# DS138-1_0-B.net
KiCad netlist of a schematic drawn in Altium Designer
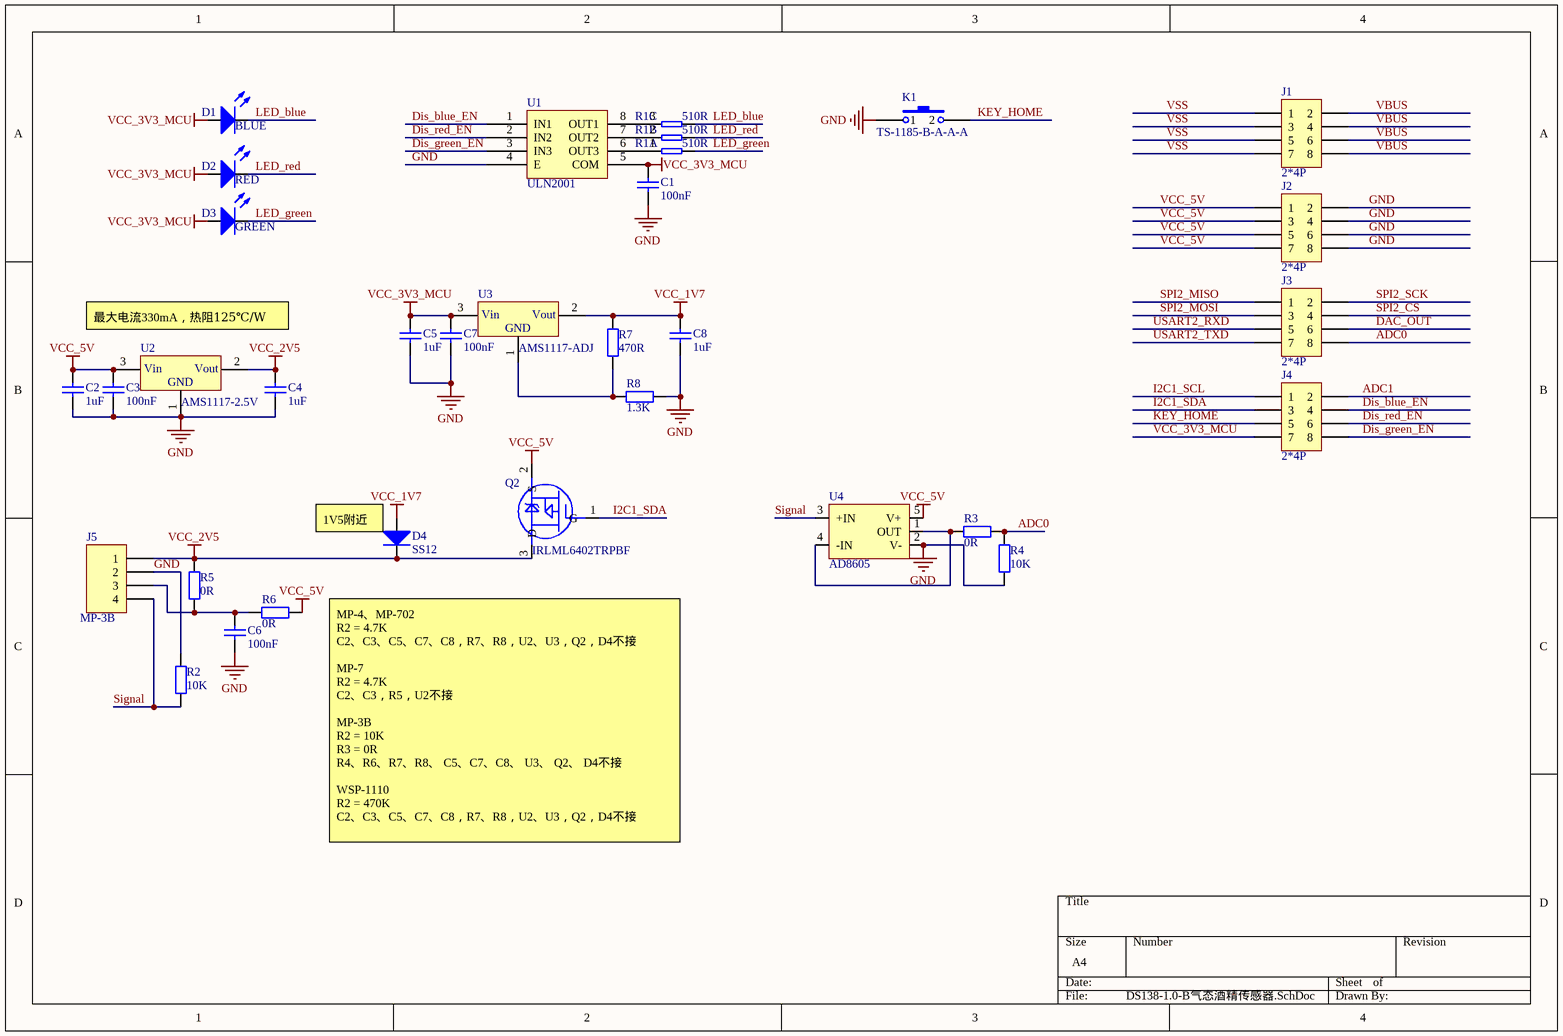
[diagram p0: DS138-1.0-B气态酒精传感器.SchDoc]

(export (version "E")
  (design (tool "Eeschema 10.0.6"))
  (components
    (comp (ref "C1")
      (value "100nF")
      (footprint "0603CAP")
      (description "贴片电容")
      (fields (field (name "Comment") "SMDCAP00013"))
      (libsource (lib "AD_SCH") (part "MLCC 100nF 50V ±10％ 0603"))
    )
    (comp (ref "C2")
      (value "1uF")
      (footprint "0603CAP")
      (description "贴片电容")
      (fields (field (name "Comment") "SMDCAP00015"))
      (libsource (lib "AD_SCH") (part "MLCC 1uF 50V ±10％ 0603"))
    )
    (comp (ref "C3")
      (value "100nF")
      (footprint "0603CAP")
      (description "贴片电容")
      (fields (field (name "Comment") "SMDCAP00013"))
      (libsource (lib "AD_SCH") (part "MLCC 100nF 50V ±10％ 0603"))
    )
    (comp (ref "C4")
      (value "1uF")
      (footprint "0603CAP")
      (description "贴片电容")
      (fields (field (name "Comment") "SMDCAP00015"))
      (libsource (lib "AD_SCH") (part "MLCC 1uF 50V ±10％ 0603"))
    )
    (comp (ref "C5")
      (value "1uF")
      (footprint "0603CAP")
      (description "贴片电容")
      (fields (field (name "Comment") "SMDCAP00015"))
      (libsource (lib "AD_SCH") (part "MLCC 1uF 50V ±10％ 0603"))
    )
    (comp (ref "C6")
      (value "100nF")
      (footprint "0603CAP")
      (description "贴片电容")
      (fields (field (name "Comment") "SMDCAP00013"))
      (libsource (lib "AD_SCH") (part "MLCC 100nF 50V ±10％ 0603"))
    )
    (comp (ref "C7")
      (value "100nF")
      (footprint "0603CAP")
      (description "贴片电容")
      (fields (field (name "Comment") "SMDCAP00013"))
      (libsource (lib "AD_SCH") (part "MLCC 100nF 50V ±10％ 0603"))
    )
    (comp (ref "C8")
      (value "1uF")
      (footprint "0603CAP")
      (description "贴片电容")
      (fields (field (name "Comment") "SMDCAP00015"))
      (libsource (lib "AD_SCH") (part "MLCC 1uF 50V ±10％ 0603"))
    )
    (comp (ref "D1")
      (value "BLUE")
      (footprint "LED_0805")
      (description "贴片LED")
      (fields (field (name "Comment") "SMDLED00010"))
      (libsource (lib "AD_SCH") (part "Chip 蓝色LED 0805"))
    )
    (comp (ref "D2")
      (value "RED")
      (footprint "LED_0805")
      (description "贴片LED")
      (fields (field (name "Comment") "SMDLED00003"))
      (libsource (lib "AD_SCH") (part "Chip 红色LED 0805"))
    )
    (comp (ref "D3")
      (value "GREEN")
      (footprint "LED_0805")
      (description "贴片LED")
      (fields (field (name "Comment") "Chip 翠绿LED 0805"))
      (libsource (lib "AD_SCH") (part "Chip 翠绿LED 0805"))
    )
    (comp (ref "D4")
      (value "SS12")
      (footprint "SMA/DO-214AC")
      (description "贴片肖特基二极管")
      (fields (field (name "Comment") "SMDDIODE06003"))
      (libsource (lib "AD_SCH") (part "SS12 SMA/DO-214AC（1N5817）"))
    )
    (comp (ref "J1")
      (value "2*4P")
      (footprint "X1321WVS-2x04J-C40D53")
      (description "双排针2x4P 立贴 1.27mm")
      (fields (field (name "Comment") "X1321WVS-2x04J-C40D53"))
      (libsource (lib "AD_SCH") (part "X1321WVS-2x04J-C40D53"))
    )
    (comp (ref "J2")
      (value "2*4P")
      (footprint "X1321WVS-2x04J-C40D53")
      (description "双排针2x4P 立贴 1.27mm")
      (fields (field (name "Comment") "X1321WVS-2x04J-C40D53"))
      (libsource (lib "AD_SCH") (part "X1321WVS-2x04J-C40D53"))
    )
    (comp (ref "J3")
      (value "2*4P")
      (footprint "X1321WVS-2x04J-C40D53")
      (description "双排针2x4P 立贴 1.27mm")
      (fields (field (name "Comment") "X1321WVS-2x04J-C40D53"))
      (libsource (lib "AD_SCH") (part "X1321WVS-2x04J-C40D53"))
    )
    (comp (ref "J4")
      (value "2*4P")
      (footprint "X1321WVS-2x04J-C40D53")
      (description "双排针2x4P 立贴 1.27mm")
      (fields (field (name "Comment") "X1321WVS-2x04J-C40D53"))
      (libsource (lib "AD_SCH") (part "X1321WVS-2x04J-C40D53"))
    )
    (comp (ref "J5")
      (value "MP-3B")
      (footprint "SIP4")
      (fields (field (name "Comment") "SL000000042"))
      (libsource (lib "AD_SCH") (part "DIP4 单排直针 间距2.54mm 针长11mm 铜"))
    )
    (comp (ref "K1")
      (value "TS-1185-B-A-A-A")
      (footprint "KEY_TS-1185-x-A-A-A")
      (description "轻触开关")
      (libsource (lib "AD_SCH") (part "TS-1185-B-A-A-A"))
    )
    (comp (ref "Q2")
      (value "IRLML6402TRPBF")
      (footprint "SOT23")
      (description "贴片P-MOS管")
      (fields (field (name "Comment") "SMDPMOS00001"))
      (libsource (lib "AD_SCH") (part "IRLML6402TRPBF SOT-23 IR"))
    )
    (comp (ref "R1")
      (value "510R")
      (footprint "0603RES_Pack4")
      (description "贴片排阻")
      (fields (field (name "Comment") "SMDRES05003"))
      (libsource (lib "AD_SCH") (part "Chip R*4 510R 1/16W ±5％ 0603"))
    )
    (comp (ref "R2")
      (value "10K")
      (footprint "0603RES")
      (description "贴片电阻")
      (fields (field (name "Comment") "SMDRES00056"))
      (libsource (lib "AD_SCH") (part "Chip 10K 1/16W ±1％ 0603"))
    )
    (comp (ref "R3")
      (value "0R")
      (footprint "0603RES")
      (description "贴片电阻")
      (fields (field (name "Comment") "Chip 0R 1/16W ±1％ 0603"))
      (libsource (lib "AD_SCH") (part "Chip 0R 1/16W ±1％ 0603"))
    )
    (comp (ref "R4")
      (value "10K")
      (footprint "0603RES")
      (description "贴片电阻")
      (fields (field (name "Comment") "SMDRES00056"))
      (libsource (lib "AD_SCH") (part "Chip 10K 1/16W ±1％ 0603"))
    )
    (comp (ref "R5")
      (value "0R")
      (footprint "0603RES")
      (description "贴片电阻")
      (fields (field (name "Comment") "Chip 0R 1/16W ±1％ 0603"))
      (libsource (lib "") (part "Chip 0R 1/16W ±1％ 0603_1"))
    )
    (comp (ref "R6")
      (value "0R")
      (footprint "0603RES")
      (description "贴片电阻")
      (fields (field (name "Comment") "Chip 0R 1/16W ±1％ 0603"))
      (libsource (lib "AD_SCH") (part "Chip 0R 1/16W ±1％ 0603"))
    )
    (comp (ref "R7")
      (value "470R")
      (footprint "0603RES")
      (description "贴片电阻")
      (fields (field (name "Comment") "SMDRES00027"))
      (libsource (lib "AD_SCH") (part "Chip 470R 1/16W ±1％ 0603"))
    )
    (comp (ref "R8")
      (value "1.3K")
      (footprint "0603RES")
      (description "贴片电阻")
      (fields (field (name "Comment") "SMDRES00038"))
      (libsource (lib "AD_SCH") (part "Chip 1.3K 1/16W ±1％ 0603"))
    )
    (comp (ref "U1")
      (value "ULN2001")
      (footprint "SO-8")
      (description "电机驱动芯片")
      (fields (field (name "Comment") "SMDIC000018"))
      (libsource (lib "AD_SCH") (part "ULN2001 SOP-8"))
    )
    (comp (ref "U2")
      (value "AMS1117-2.5V")
      (footprint "SOT223")
      (description "稳压芯片")
      (fields (field (name "Comment") "SMDIC000020"))
      (libsource (lib "AD_SCH") (part "AMS1117-3.3V SOT-223"))
    )
    (comp (ref "U3")
      (value "AMS1117-ADJ")
      (footprint "SOT223")
      (description "稳压芯片")
      (fields (field (name "Comment") "SMDIC000020"))
      (libsource (lib "AD_SCH") (part "AMS1117-3.3V SOT-223"))
    )
    (comp (ref "U4")
      (value "AD8605")
      (footprint "SOT23-5")
      (description "运放芯片")
      (libsource (lib "AD_SCH") (part "AD8605 SOT23-5"))
    )
  )
  (nets
    (net (code "1") (name "/ADC0") (class "Default")
      (node (ref "J3") (pin "8") (pinfunction "8_8") (pintype "passive"))
      (node (ref "R3") (pin "1") (pinfunction "1_1") (pintype "passive"))
      (node (ref "R4") (pin "1") (pinfunction "1_1") (pintype "passive"))
    )
    (net (code "2") (name "/ADC1") (class "Default")
      (node (ref "J4") (pin "2") (pinfunction "2_2") (pintype "passive"))
    )
    (net (code "3") (name "/DAC_OUT") (class "Default")
      (node (ref "J3") (pin "6") (pinfunction "6_6") (pintype "passive"))
    )
    (net (code "4") (name "/Dis_blue_EN") (class "Default")
      (node (ref "J4") (pin "4") (pinfunction "4_4") (pintype "passive"))
      (node (ref "U1") (pin "1") (pinfunction "IN1_1") (pintype "passive"))
    )
    (net (code "5") (name "/Dis_green_EN") (class "Default")
      (node (ref "J4") (pin "8") (pinfunction "8_8") (pintype "passive"))
      (node (ref "U1") (pin "3") (pinfunction "IN3_3") (pintype "passive"))
    )
    (net (code "6") (name "/Dis_red_EN") (class "Default")
      (node (ref "J4") (pin "6") (pinfunction "6_6") (pintype "passive"))
      (node (ref "U1") (pin "2") (pinfunction "IN2_2") (pintype "passive"))
    )
    (net (code "7") (name "/I2C1_SCL") (class "Default")
      (node (ref "J4") (pin "1") (pinfunction "1_1") (pintype "passive"))
    )
    (net (code "8") (name "/I2C1_SDA") (class "Default")
      (node (ref "J4") (pin "3") (pinfunction "3_3") (pintype "passive"))
      (node (ref "Q2") (pin "1") (pinfunction "G_1") (pintype "passive"))
    )
    (net (code "9") (name "/KEY_HOME") (class "Default")
      (node (ref "J4") (pin "5") (pinfunction "5_5") (pintype "passive"))
      (node (ref "K1") (pin "2") (pinfunction "2_2") (pintype "passive"))
    )
    (net (code "10") (name "/LED_blue") (class "Default")
      (node (ref "D1") (pin "2") (pinfunction "K_2") (pintype "passive"))
      (node (ref "R1") (pin "6") (pinfunction "6_6") (pintype "passive"))
    )
    (net (code "11") (name "/LED_green") (class "Default")
      (node (ref "D3") (pin "2") (pinfunction "K_2") (pintype "passive"))
      (node (ref "R1") (pin "8") (pinfunction "8_8") (pintype "passive"))
    )
    (net (code "12") (name "/LED_red") (class "Default")
      (node (ref "D2") (pin "2") (pinfunction "K_2") (pintype "passive"))
      (node (ref "R1") (pin "7") (pinfunction "7_7") (pintype "passive"))
    )
    (net (code "13") (name "/SPI2_CS") (class "Default")
      (node (ref "J3") (pin "4") (pinfunction "4_4") (pintype "passive"))
    )
    (net (code "14") (name "/SPI2_MISO") (class "Default")
      (node (ref "J3") (pin "1") (pinfunction "1_1") (pintype "passive"))
    )
    (net (code "15") (name "/SPI2_MOSI") (class "Default")
      (node (ref "J3") (pin "3") (pinfunction "3_3") (pintype "passive"))
    )
    (net (code "16") (name "/SPI2_SCK") (class "Default")
      (node (ref "J3") (pin "2") (pinfunction "2_2") (pintype "passive"))
    )
    (net (code "17") (name "/Signal") (class "Default")
      (node (ref "J5") (pin "4") (pinfunction "4_4") (pintype "passive"))
      (node (ref "R2") (pin "2") (pinfunction "2_2") (pintype "passive"))
      (node (ref "U4") (pin "3") (pinfunction "+IN_3") (pintype "passive"))
    )
    (net (code "18") (name "/USART2_RXD") (class "Default")
      (node (ref "J3") (pin "5") (pinfunction "5_5") (pintype "passive"))
    )
    (net (code "19") (name "/USART2_TXD") (class "Default")
      (node (ref "J3") (pin "7") (pinfunction "7_7") (pintype "passive"))
    )
    (net (code "20") (name "/VBUS") (class "Default")
      (node (ref "J1") (pin "2") (pinfunction "2_2") (pintype "passive"))
      (node (ref "J1") (pin "4") (pinfunction "4_4") (pintype "passive"))
      (node (ref "J1") (pin "6") (pinfunction "6_6") (pintype "passive"))
      (node (ref "J1") (pin "8") (pinfunction "8_8") (pintype "passive"))
    )
    (net (code "21") (name "/VSS") (class "Default")
      (node (ref "J1") (pin "1") (pinfunction "1_1") (pintype "passive"))
      (node (ref "J1") (pin "3") (pinfunction "3_3") (pintype "passive"))
      (node (ref "J1") (pin "5") (pinfunction "5_5") (pintype "passive"))
      (node (ref "J1") (pin "7") (pinfunction "7_7") (pintype "passive"))
    )
    (net (code "22") (name "GND") (class "Default")
      (node (ref "C1") (pin "1") (pinfunction "1_1") (pintype "passive"))
      (node (ref "C2") (pin "1") (pinfunction "1_1") (pintype "passive"))
      (node (ref "C3") (pin "1") (pinfunction "1_1") (pintype "passive"))
      (node (ref "C4") (pin "1") (pinfunction "1_1") (pintype "passive"))
      (node (ref "C5") (pin "1") (pinfunction "1_1") (pintype "passive"))
      (node (ref "C6") (pin "1") (pinfunction "1_1") (pintype "passive"))
      (node (ref "C7") (pin "1") (pinfunction "1_1") (pintype "passive"))
      (node (ref "C8") (pin "1") (pinfunction "1_1") (pintype "passive"))
      (node (ref "J2") (pin "2") (pinfunction "2_2") (pintype "passive"))
      (node (ref "J2") (pin "4") (pinfunction "4_4") (pintype "passive"))
      (node (ref "J2") (pin "6") (pinfunction "6_6") (pintype "passive"))
      (node (ref "J2") (pin "8") (pinfunction "8_8") (pintype "passive"))
      (node (ref "J5") (pin "2") (pinfunction "2_2") (pintype "passive"))
      (node (ref "K1") (pin "1") (pinfunction "1_1") (pintype "passive"))
      (node (ref "R2") (pin "1") (pinfunction "1_1") (pintype "passive"))
      (node (ref "R4") (pin "2") (pinfunction "2_2") (pintype "passive"))
      (node (ref "R8") (pin "2") (pinfunction "2_2") (pintype "passive"))
      (node (ref "U1") (pin "4") (pinfunction "E_4") (pintype "passive"))
      (node (ref "U2") (pin "1") (pinfunction "GND_1") (pintype "passive"))
      (node (ref "U4") (pin "2") (pinfunction "V-_2") (pintype "passive"))
    )
    (net (code "23") (name "Net-(C6-Pad2)") (class "Default")
      (node (ref "C6") (pin "2") (pinfunction "2_2") (pintype "passive"))
      (node (ref "J5") (pin "3") (pinfunction "3_3") (pintype "passive"))
      (node (ref "R5") (pin "1") (pinfunction "1_1") (pintype "passive"))
      (node (ref "R6") (pin "2") (pinfunction "2_2") (pintype "passive"))
    )
    (net (code "24") (name "Net-(U1-OUT1)") (class "Default")
      (node (ref "R1") (pin "3") (pinfunction "3_3") (pintype "passive"))
      (node (ref "U1") (pin "8") (pinfunction "OUT1_8") (pintype "passive"))
    )
    (net (code "25") (name "Net-(U1-OUT2)") (class "Default")
      (node (ref "R1") (pin "2") (pinfunction "2_2") (pintype "passive"))
      (node (ref "U1") (pin "7") (pinfunction "OUT2_7") (pintype "passive"))
    )
    (net (code "26") (name "Net-(U1-OUT3)") (class "Default")
      (node (ref "R1") (pin "1") (pinfunction "1_1") (pintype "passive"))
      (node (ref "U1") (pin "6") (pinfunction "OUT3_6") (pintype "passive"))
    )
    (net (code "27") (name "Net-(U3-GND)") (class "Default")
      (node (ref "R7") (pin "1") (pinfunction "1_1") (pintype "passive"))
      (node (ref "R8") (pin "1") (pinfunction "1_1") (pintype "passive"))
      (node (ref "U3") (pin "1") (pinfunction "GND_1") (pintype "passive"))
    )
    (net (code "28") (name "Net-(U4--IN)") (class "Default")
      (node (ref "R3") (pin "2") (pinfunction "2_2") (pintype "passive"))
      (node (ref "U4") (pin "1") (pinfunction "OUT_1") (pintype "passive"))
      (node (ref "U4") (pin "4") (pinfunction "-IN_4") (pintype "passive"))
    )
    (net (code "29") (name "VCC_1V7") (class "Default")
      (node (ref "C8") (pin "2") (pinfunction "2_2") (pintype "passive"))
      (node (ref "D4") (pin "1") (pinfunction "A_1") (pintype "passive"))
      (node (ref "R7") (pin "2") (pinfunction "2_2") (pintype "passive"))
      (node (ref "U3") (pin "2") (pinfunction "Vout_2") (pintype "passive"))
    )
    (net (code "30") (name "VCC_2V5") (class "Default")
      (node (ref "C4") (pin "2") (pinfunction "2_2") (pintype "passive"))
      (node (ref "D4") (pin "2") (pinfunction "K_2") (pintype "passive"))
      (node (ref "J5") (pin "1") (pinfunction "1_1") (pintype "passive"))
      (node (ref "Q2") (pin "3") (pinfunction "D_3") (pintype "passive"))
      (node (ref "R5") (pin "2") (pinfunction "2_2") (pintype "passive"))
      (node (ref "U2") (pin "2") (pinfunction "Vout_2") (pintype "passive"))
    )
    (net (code "31") (name "VCC_3V3_MCU") (class "Default")
      (node (ref "C1") (pin "2") (pinfunction "2_2") (pintype "passive"))
      (node (ref "C5") (pin "2") (pinfunction "2_2") (pintype "passive"))
      (node (ref "C7") (pin "2") (pinfunction "2_2") (pintype "passive"))
      (node (ref "D1") (pin "1") (pinfunction "A_1") (pintype "passive"))
      (node (ref "D2") (pin "1") (pinfunction "A_1") (pintype "passive"))
      (node (ref "D3") (pin "1") (pinfunction "A_1") (pintype "passive"))
      (node (ref "J4") (pin "7") (pinfunction "7_7") (pintype "passive"))
      (node (ref "U1") (pin "5") (pinfunction "COM_5") (pintype "passive"))
      (node (ref "U3") (pin "3") (pinfunction "Vin_3") (pintype "passive"))
    )
    (net (code "32") (name "VCC_5V") (class "Default")
      (node (ref "C2") (pin "2") (pinfunction "2_2") (pintype "passive"))
      (node (ref "C3") (pin "2") (pinfunction "2_2") (pintype "passive"))
      (node (ref "J2") (pin "1") (pinfunction "1_1") (pintype "passive"))
      (node (ref "J2") (pin "3") (pinfunction "3_3") (pintype "passive"))
      (node (ref "J2") (pin "5") (pinfunction "5_5") (pintype "passive"))
      (node (ref "J2") (pin "7") (pinfunction "7_7") (pintype "passive"))
      (node (ref "Q2") (pin "2") (pinfunction "S_2") (pintype "passive"))
      (node (ref "R6") (pin "1") (pinfunction "1_1") (pintype "passive"))
      (node (ref "U2") (pin "3") (pinfunction "Vin_3") (pintype "passive"))
      (node (ref "U4") (pin "5") (pinfunction "V+_5") (pintype "passive"))
    )
  )
)
